# multi-vca.net
KiCad netlist of a schematic drawn in EAGLE
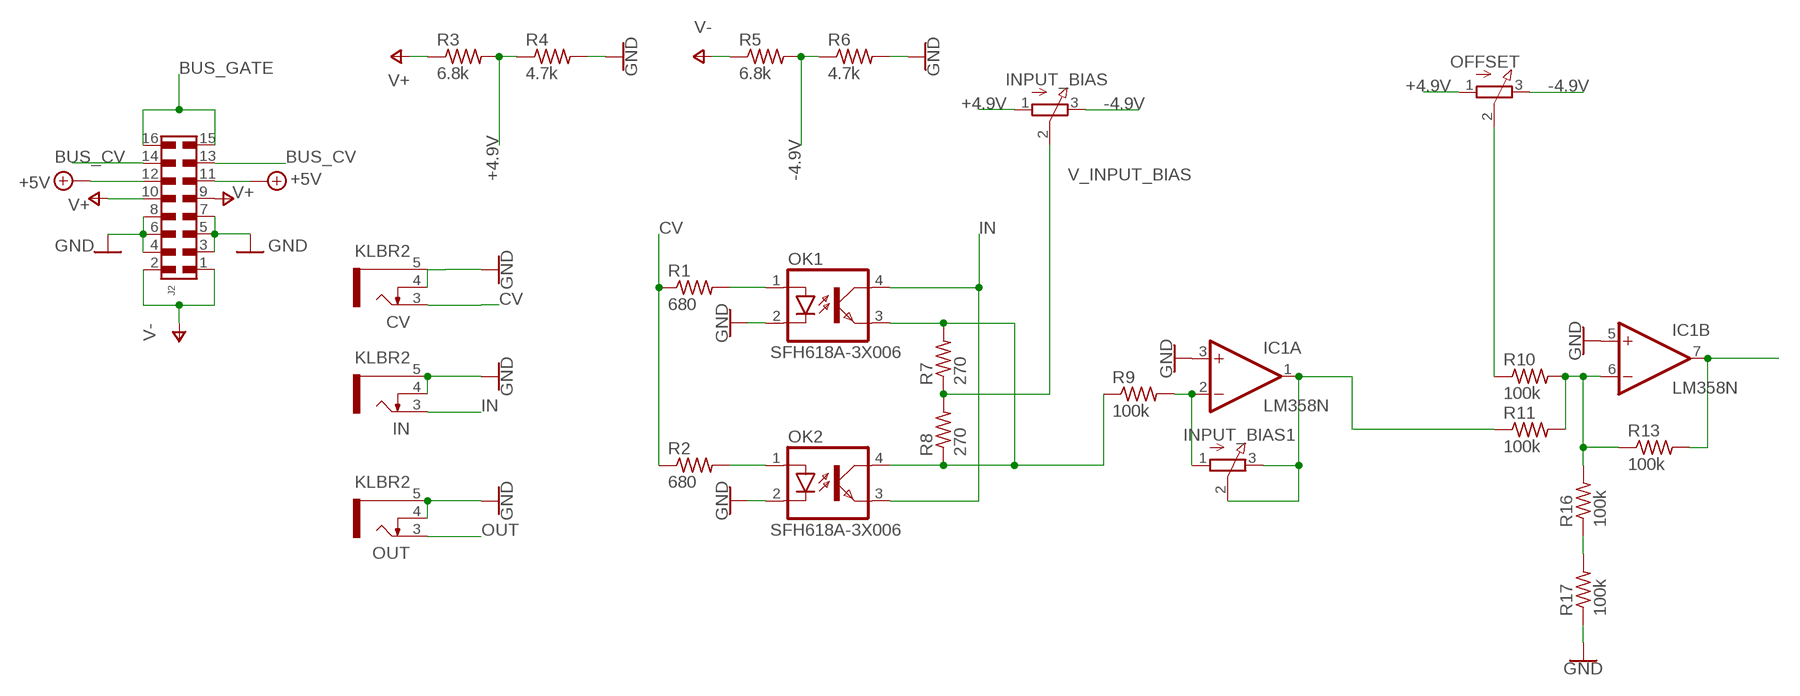
[diagram p0: schematic, sheet 1]

(export (version "E")
  (design (tool "Eeschema 10.0.6"))
  (components
    (comp (ref "CV")
      (value "KLBR2")
      (footprint "eagle-import:KLBR2")
      (libsource (lib "eagle-import") (part "KLBR?2"))
    )
    (comp (ref "IC1")
      (value "LM358N")
      (footprint "eagle-import:DIL08")
      (libsource (lib "eagle-import") (part "LM358N"))
    )
    (comp (ref "IN")
      (value "KLBR2")
      (footprint "eagle-import:KLBR2")
      (libsource (lib "eagle-import") (part "KLBR?2"))
    )
    (comp (ref "INPUT_BIAS")
      (value "3RP/1610N")
      (footprint "eagle-import:3RP_1610N")
      (libsource (lib "eagle-import") (part "3RP/1610N"))
    )
    (comp (ref "INPUT_BIAS1")
      (value "3RP/1610N")
      (footprint "eagle-import:3RP_1610N")
      (libsource (lib "eagle-import") (part "3RP/1610N"))
    )
    (comp (ref "J2")
      (value "6120XX20621_61201620621")
      (footprint "eagle-import:61201620621")
      (libsource (lib "eagle-import") (part "6120XX20621_61201620621"))
    )
    (comp (ref "OFFSET")
      (value "3RP/1610N")
      (footprint "eagle-import:3RP_1610N")
      (libsource (lib "eagle-import") (part "3RP/1610N"))
    )
    (comp (ref "OK1")
      (value "SFH618A-3X006")
      (footprint "eagle-import:DIP4-400")
      (libsource (lib "eagle-import") (part "SFH618?A-3X006"))
    )
    (comp (ref "OK2")
      (value "SFH618A-3X006")
      (footprint "eagle-import:DIP4-400")
      (libsource (lib "eagle-import") (part "SFH618?A-3X006"))
    )
    (comp (ref "OUT")
      (value "KLBR2")
      (footprint "eagle-import:KLBR2")
      (libsource (lib "eagle-import") (part "KLBR?2"))
    )
    (comp (ref "R1")
      (value "680")
      (footprint "eagle-import:0204_7")
      (libsource (lib "eagle-import") (part "R-US_0204/7"))
    )
    (comp (ref "R2")
      (value "680")
      (footprint "eagle-import:0204_7")
      (libsource (lib "eagle-import") (part "R-US_0204/7"))
    )
    (comp (ref "R3")
      (value "6.8k")
      (footprint "eagle-import:0204_7")
      (libsource (lib "eagle-import") (part "R-US_0204/7"))
    )
    (comp (ref "R4")
      (value "4.7k")
      (footprint "eagle-import:0204_7")
      (libsource (lib "eagle-import") (part "R-US_0204/7"))
    )
    (comp (ref "R5")
      (value "6.8k")
      (footprint "eagle-import:0204_7")
      (libsource (lib "eagle-import") (part "R-US_0204/7"))
    )
    (comp (ref "R6")
      (value "4.7k")
      (footprint "eagle-import:0204_7")
      (libsource (lib "eagle-import") (part "R-US_0204/7"))
    )
    (comp (ref "R7")
      (value "270")
      (footprint "eagle-import:0204_7")
      (libsource (lib "eagle-import") (part "R-US_0204/7"))
    )
    (comp (ref "R8")
      (value "270")
      (footprint "eagle-import:0204_7")
      (libsource (lib "eagle-import") (part "R-US_0204/7"))
    )
    (comp (ref "R9")
      (value "100k")
      (footprint "eagle-import:0204_7")
      (libsource (lib "eagle-import") (part "R-US_0204/7"))
    )
    (comp (ref "R10")
      (value "100k")
      (footprint "eagle-import:0204_7")
      (libsource (lib "eagle-import") (part "R-US_0204/7"))
    )
    (comp (ref "R11")
      (value "100k")
      (footprint "eagle-import:0204_7")
      (libsource (lib "eagle-import") (part "R-US_0204/7"))
    )
    (comp (ref "R13")
      (value "100k")
      (footprint "eagle-import:0204_7")
      (libsource (lib "eagle-import") (part "R-US_0204/7"))
    )
    (comp (ref "R16")
      (value "100k")
      (footprint "eagle-import:0204_7")
      (libsource (lib "eagle-import") (part "R-US_0204/7"))
    )
    (comp (ref "R17")
      (value "100k")
      (footprint "eagle-import:0204_7")
      (libsource (lib "eagle-import") (part "R-US_0204/7"))
    )
  )
  (nets
    (net (code "1") (name "+5V") (class "Default")
      (node (ref "J2") (pin "11") (pinfunction "11_11") (pintype "passive"))
      (node (ref "J2") (pin "12") (pinfunction "12_12") (pintype "passive"))
    )
    (net (code "2") (name "/+4.9V") (class "Default")
      (node (ref "INPUT_BIAS") (pin "1") (pinfunction "A_1") (pintype "passive"))
      (node (ref "OFFSET") (pin "1") (pinfunction "A_1") (pintype "passive"))
      (node (ref "R3") (pin "2") (pinfunction "2_2") (pintype "passive"))
      (node (ref "R4") (pin "1") (pinfunction "1_1") (pintype "passive"))
    )
    (net (code "3") (name "/-4.9V") (class "Default")
      (node (ref "INPUT_BIAS") (pin "3") (pinfunction "E_3") (pintype "passive"))
      (node (ref "OFFSET") (pin "3") (pinfunction "E_3") (pintype "passive"))
      (node (ref "R5") (pin "2") (pinfunction "2_2") (pintype "passive"))
      (node (ref "R6") (pin "1") (pinfunction "1_1") (pintype "passive"))
    )
    (net (code "4") (name "/BUS_CV") (class "Default")
      (node (ref "J2") (pin "13") (pinfunction "13_13") (pintype "passive"))
      (node (ref "J2") (pin "14") (pinfunction "14_14") (pintype "passive"))
    )
    (net (code "5") (name "/BUS_GATE") (class "Default")
      (node (ref "J2") (pin "15") (pinfunction "15_15") (pintype "passive"))
      (node (ref "J2") (pin "16") (pinfunction "16_16") (pintype "passive"))
    )
    (net (code "6") (name "/CV") (class "Default")
      (node (ref "CV") (pin "3") (pinfunction "3_3") (pintype "passive"))
      (node (ref "R1") (pin "1") (pinfunction "1_1") (pintype "passive"))
      (node (ref "R2") (pin "1") (pinfunction "1_1") (pintype "passive"))
    )
    (net (code "7") (name "/IN") (class "Default")
      (node (ref "IN") (pin "3") (pinfunction "3_3") (pintype "passive"))
      (node (ref "OK1") (pin "4") (pinfunction "COL_4") (pintype "passive"))
      (node (ref "OK2") (pin "3") (pinfunction "EMIT_3") (pintype "passive"))
    )
    (net (code "8") (name "/OUT") (class "Default")
      (node (ref "OUT") (pin "3") (pinfunction "3_3") (pintype "passive"))
    )
    (net (code "9") (name "/V_INPUT_BIAS") (class "Default")
      (node (ref "INPUT_BIAS") (pin "2") (pinfunction "S_2") (pintype "passive"))
      (node (ref "R7") (pin "1") (pinfunction "1_1") (pintype "passive"))
      (node (ref "R8") (pin "2") (pinfunction "2_2") (pintype "passive"))
    )
    (net (code "10") (name "GND") (class "Default")
      (node (ref "CV") (pin "4") (pinfunction "4_4") (pintype "passive"))
      (node (ref "CV") (pin "5") (pinfunction "5_5") (pintype "passive"))
      (node (ref "IC1") (pin "3") (pinfunction "+IN_3") (pintype "input"))
      (node (ref "IC1") (pin "5") (pinfunction "+IN_5") (pintype "input"))
      (node (ref "IN") (pin "4") (pinfunction "4_4") (pintype "passive"))
      (node (ref "IN") (pin "5") (pinfunction "5_5") (pintype "passive"))
      (node (ref "J2") (pin "3") (pinfunction "3_3") (pintype "passive"))
      (node (ref "J2") (pin "4") (pinfunction "4_4") (pintype "passive"))
      (node (ref "J2") (pin "5") (pinfunction "5_5") (pintype "passive"))
      (node (ref "J2") (pin "6") (pinfunction "6_6") (pintype "passive"))
      (node (ref "J2") (pin "7") (pinfunction "7_7") (pintype "passive"))
      (node (ref "J2") (pin "8") (pinfunction "8_8") (pintype "passive"))
      (node (ref "OK1") (pin "2") (pinfunction "C_2") (pintype "passive"))
      (node (ref "OK2") (pin "2") (pinfunction "C_2") (pintype "passive"))
      (node (ref "OUT") (pin "4") (pinfunction "4_4") (pintype "passive"))
      (node (ref "OUT") (pin "5") (pinfunction "5_5") (pintype "passive"))
      (node (ref "R17") (pin "1") (pinfunction "1_1") (pintype "passive"))
      (node (ref "R4") (pin "2") (pinfunction "2_2") (pintype "passive"))
      (node (ref "R6") (pin "2") (pinfunction "2_2") (pintype "passive"))
    )
    (net (code "11") (name "Net-(IC1A--IN)") (class "Default")
      (node (ref "IC1") (pin "2") (pinfunction "-IN_2") (pintype "input"))
      (node (ref "INPUT_BIAS1") (pin "1") (pinfunction "A_1") (pintype "passive"))
      (node (ref "R9") (pin "2") (pinfunction "2_2") (pintype "passive"))
    )
    (net (code "12") (name "Net-(IC1A-OUT)") (class "Default")
      (node (ref "IC1") (pin "1") (pinfunction "OUT_1") (pintype "output"))
      (node (ref "INPUT_BIAS1") (pin "2") (pinfunction "S_2") (pintype "passive"))
      (node (ref "INPUT_BIAS1") (pin "3") (pinfunction "E_3") (pintype "passive"))
      (node (ref "R11") (pin "1") (pinfunction "1_1") (pintype "passive"))
    )
    (net (code "13") (name "Net-(IC1B--IN)") (class "Default")
      (node (ref "IC1") (pin "6") (pinfunction "-IN_6") (pintype "input"))
      (node (ref "R10") (pin "2") (pinfunction "2_2") (pintype "passive"))
      (node (ref "R11") (pin "2") (pinfunction "2_2") (pintype "passive"))
      (node (ref "R13") (pin "1") (pinfunction "1_1") (pintype "passive"))
      (node (ref "R16") (pin "2") (pinfunction "2_2") (pintype "passive"))
    )
    (net (code "14") (name "Net-(IC1B-OUT)") (class "Default")
      (node (ref "IC1") (pin "7") (pinfunction "OUT_7") (pintype "output"))
      (node (ref "R13") (pin "2") (pinfunction "2_2") (pintype "passive"))
    )
    (net (code "15") (name "Net-(OFFSET-S)") (class "Default")
      (node (ref "OFFSET") (pin "2") (pinfunction "S_2") (pintype "passive"))
      (node (ref "R10") (pin "1") (pinfunction "1_1") (pintype "passive"))
    )
    (net (code "16") (name "Net-(OK1-A)") (class "Default")
      (node (ref "OK1") (pin "1") (pinfunction "A_1") (pintype "passive"))
      (node (ref "R1") (pin "2") (pinfunction "2_2") (pintype "passive"))
    )
    (net (code "17") (name "Net-(OK1-EMIT)") (class "Default")
      (node (ref "OK1") (pin "3") (pinfunction "EMIT_3") (pintype "passive"))
      (node (ref "OK2") (pin "4") (pinfunction "COL_4") (pintype "passive"))
      (node (ref "R7") (pin "2") (pinfunction "2_2") (pintype "passive"))
      (node (ref "R8") (pin "1") (pinfunction "1_1") (pintype "passive"))
      (node (ref "R9") (pin "1") (pinfunction "1_1") (pintype "passive"))
    )
    (net (code "18") (name "Net-(OK2-A)") (class "Default")
      (node (ref "OK2") (pin "1") (pinfunction "A_1") (pintype "passive"))
      (node (ref "R2") (pin "2") (pinfunction "2_2") (pintype "passive"))
    )
    (net (code "19") (name "Net-(R16-Pad1)") (class "Default")
      (node (ref "R16") (pin "1") (pinfunction "1_1") (pintype "passive"))
      (node (ref "R17") (pin "2") (pinfunction "2_2") (pintype "passive"))
    )
    (net (code "20") (name "V+") (class "Default")
      (node (ref "J2") (pin "10") (pinfunction "10_10") (pintype "passive"))
      (node (ref "J2") (pin "9") (pinfunction "9_9") (pintype "passive"))
      (node (ref "R3") (pin "1") (pinfunction "1_1") (pintype "passive"))
    )
    (net (code "21") (name "V-") (class "Default")
      (node (ref "J2") (pin "1") (pinfunction "1_1") (pintype "passive"))
      (node (ref "J2") (pin "2") (pinfunction "2_2") (pintype "passive"))
      (node (ref "R5") (pin "1") (pinfunction "1_1") (pintype "passive"))
    )
  )
)
